# Sheet1.net
KiCad netlist of a schematic drawn in Altium Designer
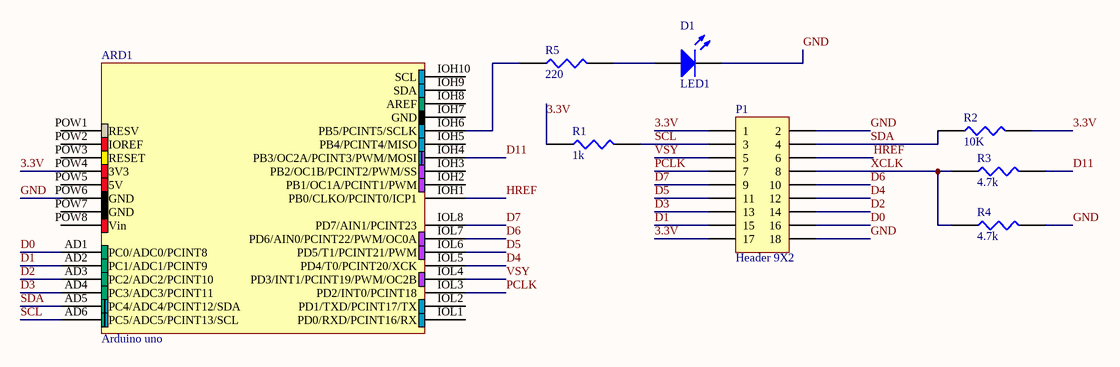
[diagram p0: Sheet1.SchDoc]

(export (version "E")
  (design (tool "Eeschema 10.0.6"))
  (components
    (comp (ref "ARD1")
      (value "Arduino uno")
      (footprint "ARDUINO_UNO")
      (description "Arduino UNO Connector")
      (libsource (lib "Arduino_UNO_MEGA2560") (part "Arduino uno"))
    )
    (comp (ref "D1")
      (value "LED1")
      (footprint "LED-1")
      (description "Typical RED GaAs LED")
      (fields (field (name "PUBLISHER") "Altium Limited"))
      (libsource (lib "Miscellaneous Devices") (part "LED1"))
    )
    (comp (ref "P1")
      (value "Header 9X2")
      (footprint "HDR2X9")
      (description "Header, 9-Pin, Dual row")
      (fields (field (name "PUBLISHER") "Altium Limited"))
      (libsource (lib "Miscellaneous Connectors") (part "Header 9X2"))
    )
    (comp (ref "R1")
      (value "1k")
      (footprint "My_axial-0.4")
      (description "resistor 1/4 wat")
      (fields (field (name "Comment") "470R"))
      (libsource (lib "Devices") (part "Res"))
    )
    (comp (ref "R2")
      (value "10K")
      (footprint "My_axial-0.4")
      (description "resistor 1/4 wat")
      (fields (field (name "Comment") "470R"))
      (libsource (lib "Devices") (part "Res"))
    )
    (comp (ref "R3")
      (value "4.7k")
      (footprint "My_axial-0.4")
      (description "resistor 1/4 wat")
      (fields (field (name "Comment") "470R"))
      (libsource (lib "Devices") (part "Res"))
    )
    (comp (ref "R4")
      (value "4.7k")
      (footprint "My_axial-0.4")
      (description "resistor 1/4 wat")
      (fields (field (name "Comment") "470R"))
      (libsource (lib "Devices") (part "Res"))
    )
    (comp (ref "R5")
      (value "220")
      (footprint "My_axial-0.4")
      (description "resistor 1/4 wat")
      (fields (field (name "Comment") "470R"))
      (libsource (lib "Devices") (part "Res"))
    )
  )
  (nets
    (net (code "1") (name "/3.3V") (class "Default")
      (node (ref "ARD1") (pin "POW4") (pinfunction "3V3_POW4") (pintype "passive"))
      (node (ref "P1") (pin "1") (pinfunction "1_1") (pintype "passive"))
      (node (ref "P1") (pin "17") (pinfunction "17_17") (pintype "passive"))
      (node (ref "R1") (pin "1") (pinfunction "1_1") (pintype "passive"))
      (node (ref "R2") (pin "2") (pinfunction "2_2") (pintype "passive"))
    )
    (net (code "2") (name "/D0") (class "Default")
      (node (ref "ARD1") (pin "AD1") (pinfunction "PC0/ADC0/PCINT8_AD1") (pintype "passive"))
      (node (ref "P1") (pin "16") (pinfunction "16_16") (pintype "passive"))
    )
    (net (code "3") (name "/D1") (class "Default")
      (node (ref "ARD1") (pin "AD2") (pinfunction "PC1/ADC1/PCINT9_AD2") (pintype "passive"))
      (node (ref "P1") (pin "15") (pinfunction "15_15") (pintype "passive"))
    )
    (net (code "4") (name "/D2") (class "Default")
      (node (ref "ARD1") (pin "AD3") (pinfunction "PC2/ADC2/PCINT10_AD3") (pintype "passive"))
      (node (ref "P1") (pin "14") (pinfunction "14_14") (pintype "passive"))
    )
    (net (code "5") (name "/D3") (class "Default")
      (node (ref "ARD1") (pin "AD4") (pinfunction "PC3/ADC3/PCINT11_AD4") (pintype "passive"))
      (node (ref "P1") (pin "13") (pinfunction "13_13") (pintype "passive"))
    )
    (net (code "6") (name "/D4") (class "Default")
      (node (ref "ARD1") (pin "IOL5") (pinfunction "PD4/T0/PCINT20/XCK_IOL5") (pintype "passive"))
      (node (ref "P1") (pin "12") (pinfunction "12_12") (pintype "passive"))
    )
    (net (code "7") (name "/D5") (class "Default")
      (node (ref "ARD1") (pin "IOL6") (pinfunction "PD5/T1/PCINT21/PWM_IOL6") (pintype "passive"))
      (node (ref "P1") (pin "11") (pinfunction "11_11") (pintype "passive"))
    )
    (net (code "8") (name "/D6") (class "Default")
      (node (ref "ARD1") (pin "IOL7") (pinfunction "PD6/AIN0/PCINT22/PWM/OC0A_IOL7") (pintype "passive"))
      (node (ref "P1") (pin "10") (pinfunction "10_10") (pintype "passive"))
    )
    (net (code "9") (name "/D7") (class "Default")
      (node (ref "ARD1") (pin "IOL8") (pinfunction "PD7/AIN1/PCINT23_IOL8") (pintype "passive"))
      (node (ref "P1") (pin "9") (pinfunction "9_9") (pintype "passive"))
    )
    (net (code "10") (name "/D11") (class "Default")
      (node (ref "ARD1") (pin "IOH4") (pinfunction "PB3/OC2A/PCINT3/PWM/MOSI_IOH4") (pintype "passive"))
      (node (ref "R3") (pin "2") (pinfunction "2_2") (pintype "passive"))
    )
    (net (code "11") (name "/GND") (class "Default")
      (node (ref "ARD1") (pin "POW6") (pinfunction "GND_POW6") (pintype "passive"))
      (node (ref "D1") (pin "2") (pinfunction "K_2") (pintype "passive"))
      (node (ref "P1") (pin "18") (pinfunction "18_18") (pintype "passive"))
      (node (ref "P1") (pin "2") (pinfunction "2_2") (pintype "passive"))
      (node (ref "R4") (pin "2") (pinfunction "2_2") (pintype "passive"))
    )
    (net (code "12") (name "/HREF") (class "Default")
      (node (ref "ARD1") (pin "IOH1") (pinfunction "PB0/CLKO/PCINT0/ICP1_IOH1") (pintype "passive"))
      (node (ref "P1") (pin "6") (pinfunction "6_6") (pintype "passive"))
    )
    (net (code "13") (name "/PCLK") (class "Default")
      (node (ref "ARD1") (pin "IOL3") (pinfunction "PD2/INT0/PCINT18_IOL3") (pintype "passive"))
      (node (ref "P1") (pin "7") (pinfunction "7_7") (pintype "passive"))
    )
    (net (code "14") (name "/SCL") (class "Default")
      (node (ref "ARD1") (pin "AD6") (pinfunction "PC5/ADC5/PCINT13/SCL_AD6") (pintype "passive"))
      (node (ref "P1") (pin "3") (pinfunction "3_3") (pintype "passive"))
      (node (ref "R1") (pin "2") (pinfunction "2_2") (pintype "passive"))
    )
    (net (code "15") (name "/SDA") (class "Default")
      (node (ref "ARD1") (pin "AD5") (pinfunction "PC4/ADC4/PCINT12/SDA_AD5") (pintype "passive"))
      (node (ref "P1") (pin "4") (pinfunction "4_4") (pintype "passive"))
      (node (ref "R2") (pin "1") (pinfunction "1_1") (pintype "passive"))
    )
    (net (code "16") (name "/VSY") (class "Default")
      (node (ref "ARD1") (pin "IOL4") (pinfunction "PD3/INT1/PCINT19/PWM/OC2B_IOL4") (pintype "passive"))
      (node (ref "P1") (pin "5") (pinfunction "5_5") (pintype "passive"))
    )
    (net (code "17") (name "/XCLK") (class "Default")
      (node (ref "P1") (pin "8") (pinfunction "8_8") (pintype "passive"))
      (node (ref "R3") (pin "1") (pinfunction "1_1") (pintype "passive"))
      (node (ref "R4") (pin "1") (pinfunction "1_1") (pintype "passive"))
    )
    (net (code "18") (name "Net-(ARD1-PB5{slash}PCINT5{slash}SCLK)") (class "Default")
      (node (ref "ARD1") (pin "IOH6") (pinfunction "PB5/PCINT5/SCLK_IOH6") (pintype "passive"))
      (node (ref "R5") (pin "1") (pinfunction "1_1") (pintype "passive"))
    )
    (net (code "19") (name "Net-(D1-A)") (class "Default")
      (node (ref "D1") (pin "1") (pinfunction "A_1") (pintype "passive"))
      (node (ref "R5") (pin "2") (pinfunction "2_2") (pintype "passive"))
    )
    (net (code "20") (name "unconnected-(ARD1-5V-PadPOW5)") (class "Default")
      (node (ref "ARD1") (pin "POW5") (pinfunction "5V_POW5") (pintype "passive"))
    )
    (net (code "21") (name "unconnected-(ARD1-AREF-PadIOH8)") (class "Default")
      (node (ref "ARD1") (pin "IOH8") (pinfunction "AREF_IOH8") (pintype "passive"))
    )
    (net (code "22") (name "unconnected-(ARD1-GND-PadIOH7)") (class "Default")
      (node (ref "ARD1") (pin "IOH7") (pinfunction "GND_IOH7") (pintype "passive"))
    )
    (net (code "23") (name "unconnected-(ARD1-GND-PadPOW7)") (class "Default")
      (node (ref "ARD1") (pin "POW7") (pinfunction "GND_POW7") (pintype "passive"))
    )
    (net (code "24") (name "unconnected-(ARD1-IOREF-PadPOW2)") (class "Default")
      (node (ref "ARD1") (pin "POW2") (pinfunction "IOREF_POW2") (pintype "passive"))
    )
    (net (code "25") (name "unconnected-(ARD1-PB1{slash}OC1A{slash}PCINT1{slash}PWM-PadIOH2)") (class "Default")
      (node (ref "ARD1") (pin "IOH2") (pinfunction "PB1/OC1A/PCINT1/PWM_IOH2") (pintype "passive"))
    )
    (net (code "26") (name "unconnected-(ARD1-PB2{slash}OC1B{slash}PCINT2{slash}PWM{slash}SS-PadIOH3)") (class "Default")
      (node (ref "ARD1") (pin "IOH3") (pinfunction "PB2/OC1B/PCINT2/PWM/SS_IOH3") (pintype "passive"))
    )
    (net (code "27") (name "unconnected-(ARD1-PB4{slash}PCINT4{slash}MISO-PadIOH5)") (class "Default")
      (node (ref "ARD1") (pin "IOH5") (pinfunction "PB4/PCINT4/MISO_IOH5") (pintype "passive"))
    )
    (net (code "28") (name "unconnected-(ARD1-PD0{slash}RXD{slash}PCINT16{slash}RX-PadIOL1)") (class "Default")
      (node (ref "ARD1") (pin "IOL1") (pinfunction "PD0/RXD/PCINT16/RX_IOL1") (pintype "passive"))
    )
    (net (code "29") (name "unconnected-(ARD1-PD1{slash}TXD{slash}PCINT17{slash}TX-PadIOL2)") (class "Default")
      (node (ref "ARD1") (pin "IOL2") (pinfunction "PD1/TXD/PCINT17/TX_IOL2") (pintype "passive"))
    )
    (net (code "30") (name "unconnected-(ARD1-RESET-PadPOW3)") (class "Default")
      (node (ref "ARD1") (pin "POW3") (pinfunction "RESET_POW3") (pintype "passive"))
    )
    (net (code "31") (name "unconnected-(ARD1-RESV-PadPOW1)") (class "Default")
      (node (ref "ARD1") (pin "POW1") (pinfunction "RESV_POW1") (pintype "passive"))
    )
    (net (code "32") (name "unconnected-(ARD1-SCL-PadIOH10)") (class "Default")
      (node (ref "ARD1") (pin "IOH10") (pinfunction "SCL_IOH10") (pintype "passive"))
    )
    (net (code "33") (name "unconnected-(ARD1-SDA-PadIOH9)") (class "Default")
      (node (ref "ARD1") (pin "IOH9") (pinfunction "SDA_IOH9") (pintype "passive"))
    )
    (net (code "34") (name "unconnected-(ARD1-Vin-PadPOW8)") (class "Default")
      (node (ref "ARD1") (pin "POW8") (pinfunction "Vin_POW8") (pintype "passive"))
    )
  )
)
